# Sheet1.net
KiCad netlist of a schematic drawn in Altium Designer
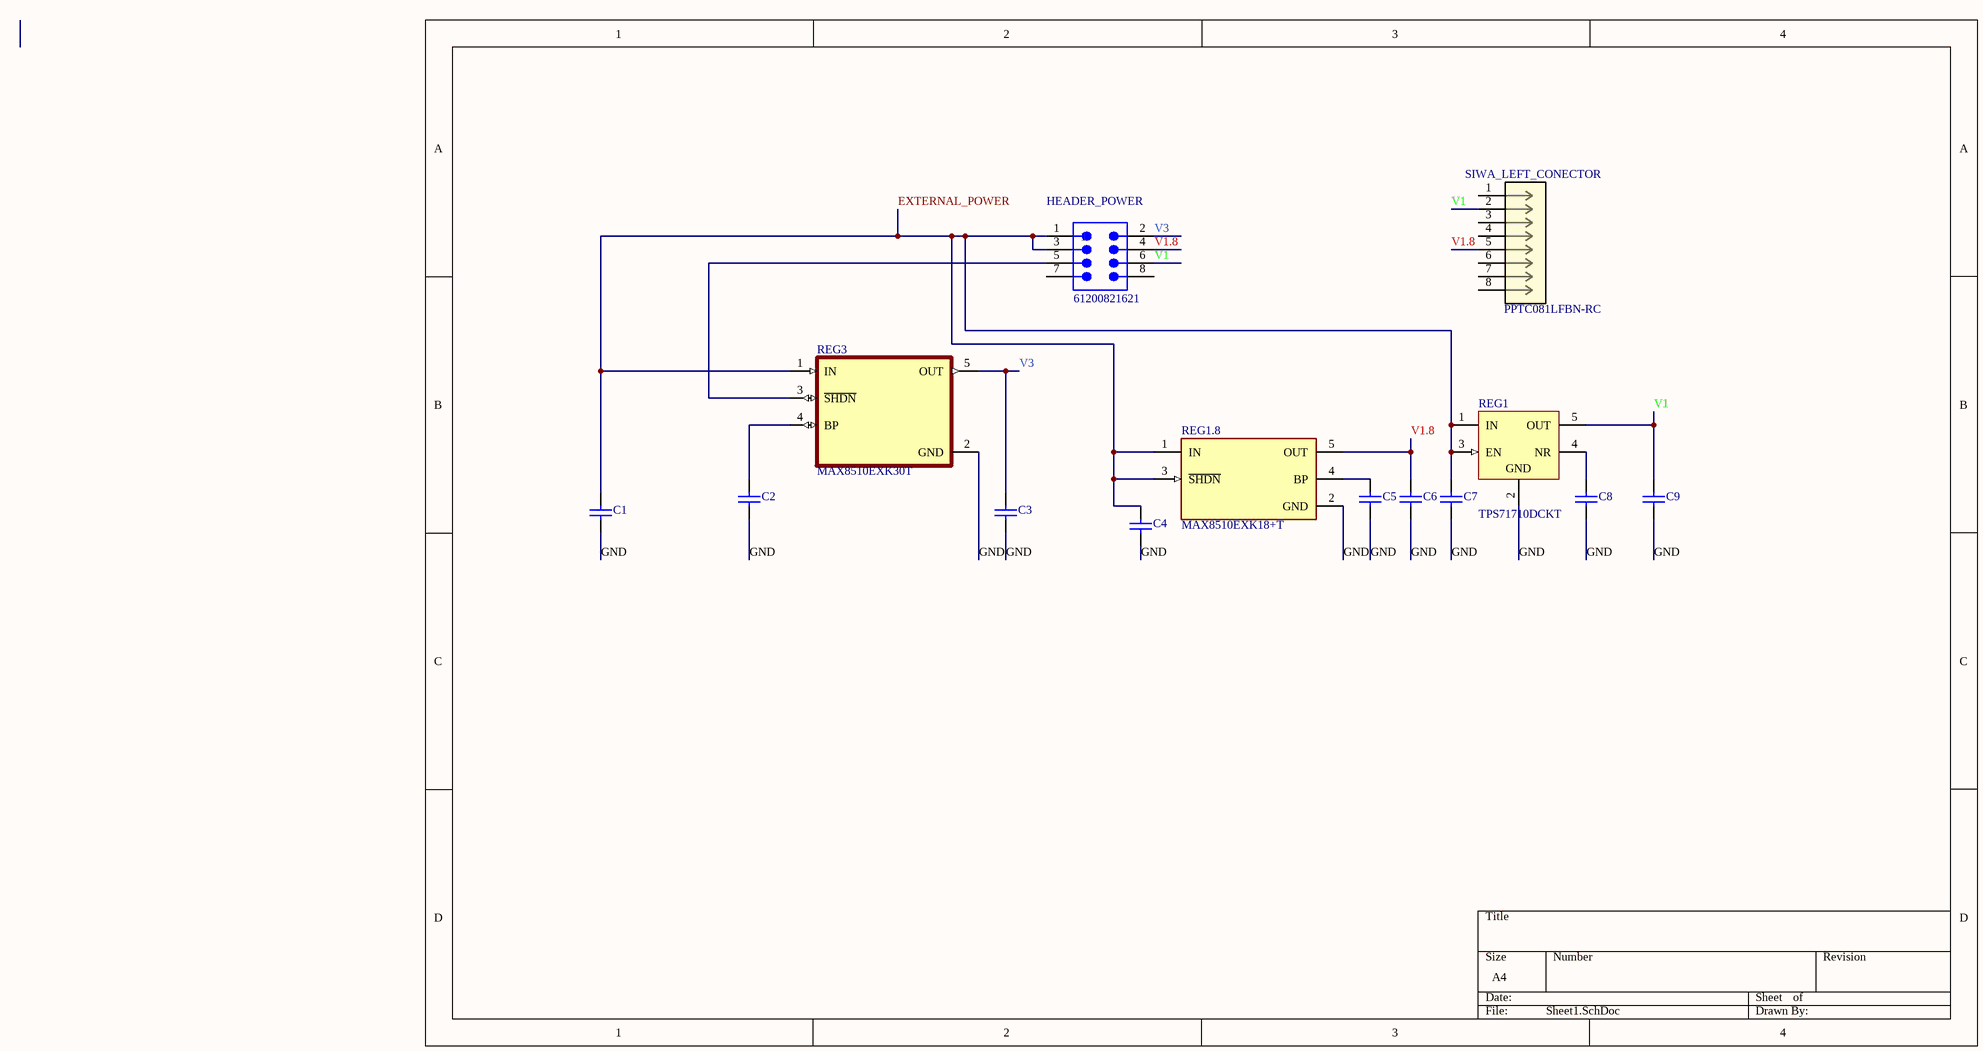
[diagram p0: Sheet1.SchDoc]

(export (version "E")
  (design (tool "Eeschema 10.0.6"))
  (components
    (comp (ref "C1")
      (value "VJ0603Y102KXJAC")
      (footprint "CAPC1608X92X38ML15T08")
      (fields (field (name "MANUFACTURER") "Vitramon"))
      (libsource (lib "Altium Content Vault") (part "CAP"))
    )
    (comp (ref "C2")
      (value "VJ0603Y102KXJAC")
      (footprint "CAPC1608X92X38ML15T08")
      (fields (field (name "MANUFACTURER") "Vitramon"))
      (libsource (lib "Altium Content Vault") (part "CAP"))
    )
    (comp (ref "C3")
      (value "VJ0603Y102KXJAC")
      (footprint "CAPC1608X92X38ML15T08")
      (fields (field (name "MANUFACTURER") "Vitramon"))
      (libsource (lib "Altium Content Vault") (part "CAP"))
    )
    (comp (ref "C4")
      (value "VJ0603Y102KXJAC")
      (footprint "CAPC1608X92X38ML15T08")
      (fields (field (name "MANUFACTURER") "Vitramon"))
      (libsource (lib "Altium Content Vault") (part "CAP"))
    )
    (comp (ref "C5")
      (value "VJ0603Y102KXJAC")
      (footprint "CAPC1608X92X38ML15T08")
      (fields (field (name "MANUFACTURER") "Vitramon"))
      (libsource (lib "Altium Content Vault") (part "CAP"))
    )
    (comp (ref "C6")
      (value "VJ0603Y102KXJAC")
      (footprint "CAPC1608X92X38ML15T08")
      (fields (field (name "MANUFACTURER") "Vitramon"))
      (libsource (lib "Altium Content Vault") (part "CAP"))
    )
    (comp (ref "C7")
      (value "VJ0603Y102KXJAC")
      (footprint "CAPC1608X92X38ML15T08")
      (fields (field (name "MANUFACTURER") "Vitramon"))
      (libsource (lib "Altium Content Vault") (part "CAP"))
    )
    (comp (ref "C8")
      (value "VJ0603Y102KXJAC")
      (footprint "CAPC1608X92X38ML15T08")
      (fields (field (name "MANUFACTURER") "Vitramon"))
      (libsource (lib "Altium Content Vault") (part "CAP"))
    )
    (comp (ref "C9")
      (value "VJ0603Y102KXJAC")
      (footprint "CAPC1608X92X38ML15T08")
      (fields (field (name "MANUFACTURER") "Vitramon"))
      (libsource (lib "Altium Content Vault") (part "CAP"))
    )
    (comp (ref "HEADER_POWER")
      (value "61200821621")
      (footprint "61200821621")
      (description "Wr-bhd; 2.54MM Pitch 8 Way 2 Row Shrouded Straight Pcb Header, Surface Mount")
      (libsource (lib "Altium Content Vault") (part "Header_Male_2R_08P"))
    )
    (comp (ref "REG1")
      (value "TPS71710DCKT")
      (footprint "DCK0005A_M")
      (fields (field (name "MANUFACTURER") "Texas Instruments"))
      (libsource (lib "Altium Content Vault") (part "TI-TPS79NXX-YYSOT5"))
    )
    (comp (ref "REG1.8")
      (value "MAX8510EXK18+T")
      (footprint "FP-X5-1-MFG")
      (description "IC REG LINEAR 1.8V 120MA SC70-5")
      (libsource (lib "Altium Content Vault") (part "355d6218c957986cfc1b3588039a240"))
    )
    (comp (ref "REG3")
      (value "MAX8510EXK30T")
      (footprint "SOT65P210X110-5N")
      (description "DoÄŸrusal Voltaj RegÃ¼latÃ¶rÃ¼ IC Pozitif Sabit 1 Ã‡Ä±kÄ±ÅŸ 120mA SC-70-5")
      (fields (field (name "MF") "Maxim Integrated Products") (field (name "MP") "MAX8510EXK30+T"))
      (libsource (lib "MAX8510EXK30T") (part "MAX8510EXK30T"))
    )
    (comp (ref "SIWA_LEFT_CONECTOR")
      (value "PPTC081LFBN-RC")
      (footprint "CONN_PPTC081LFBN-RC_SUL")
      (description "Description")
      (fields (field (name "COPYRIGHT") "Copyright (C) 2026 Ultra Librarian. All rights reserved."))
      (libsource (lib "PPTC081LFBN-RC") (part "PPTC081LFBN-RC"))
    )
  )
  (nets
    (net (code "1") (name "/EXTERNAL_POWER") (class "Default")
      (node (ref "C1") (pin "2") (pinfunction "2_2") (pintype "passive"))
      (node (ref "C4") (pin "2") (pinfunction "2_2") (pintype "passive"))
      (node (ref "C7") (pin "2") (pinfunction "2_2") (pintype "passive"))
      (node (ref "HEADER_POWER") (pin "1") (pinfunction "1_1") (pintype "passive"))
      (node (ref "HEADER_POWER") (pin "3") (pinfunction "3_3") (pintype "passive"))
      (node (ref "REG1") (pin "1") (pinfunction "IN_1") (pintype "power_in"))
      (node (ref "REG1") (pin "3") (pinfunction "EN_3") (pintype "input"))
      (node (ref "REG1.8") (pin "1") (pinfunction "IN_1") (pintype "power_in"))
      (node (ref "REG1.8") (pin "3") (pinfunction "~{SHDN}_3") (pintype "input"))
      (node (ref "REG3") (pin "1") (pinfunction "IN_1") (pintype "input"))
    )
    (net (code "2") (name "/GND") (class "Default")
      (node (ref "C1") (pin "1") (pinfunction "1_1") (pintype "passive"))
      (node (ref "C2") (pin "1") (pinfunction "1_1") (pintype "passive"))
      (node (ref "C3") (pin "1") (pinfunction "1_1") (pintype "passive"))
      (node (ref "C4") (pin "1") (pinfunction "1_1") (pintype "passive"))
      (node (ref "C5") (pin "1") (pinfunction "1_1") (pintype "passive"))
      (node (ref "C6") (pin "1") (pinfunction "1_1") (pintype "passive"))
      (node (ref "C7") (pin "1") (pinfunction "1_1") (pintype "passive"))
      (node (ref "C8") (pin "1") (pinfunction "1_1") (pintype "passive"))
      (node (ref "C9") (pin "1") (pinfunction "1_1") (pintype "passive"))
      (node (ref "REG1") (pin "2") (pinfunction "GND_2") (pintype "power_in"))
      (node (ref "REG1.8") (pin "2") (pinfunction "GND_2") (pintype "power_in"))
      (node (ref "REG3") (pin "2") (pinfunction "GND_2") (pintype "power_in"))
    )
    (net (code "3") (name "/V1") (class "Default")
      (node (ref "C9") (pin "2") (pinfunction "2_2") (pintype "passive"))
      (node (ref "HEADER_POWER") (pin "6") (pinfunction "6_6") (pintype "passive"))
      (node (ref "REG1") (pin "5") (pinfunction "OUT_5") (pintype "power_in"))
      (node (ref "SIWA_LEFT_CONECTOR") (pin "2") (pinfunction "2_2") (pintype "passive"))
    )
    (net (code "4") (name "/V1.8") (class "Default")
      (node (ref "C6") (pin "2") (pinfunction "2_2") (pintype "passive"))
      (node (ref "HEADER_POWER") (pin "4") (pinfunction "4_4") (pintype "passive"))
      (node (ref "REG1.8") (pin "5") (pinfunction "OUT_5") (pintype "power_in"))
      (node (ref "SIWA_LEFT_CONECTOR") (pin "5") (pinfunction "5_5") (pintype "passive"))
    )
    (net (code "5") (name "/V3") (class "Default")
      (node (ref "C3") (pin "2") (pinfunction "2_2") (pintype "passive"))
      (node (ref "HEADER_POWER") (pin "2") (pinfunction "2_2") (pintype "passive"))
      (node (ref "REG3") (pin "5") (pinfunction "OUT_5") (pintype "output"))
    )
    (net (code "6") (name "Net-(REG1-NR)") (class "Default")
      (node (ref "C8") (pin "2") (pinfunction "2_2") (pintype "passive"))
      (node (ref "REG1") (pin "4") (pinfunction "NR_4") (pintype "passive"))
    )
    (net (code "7") (name "Net-(REG1.8-BP)") (class "Default")
      (node (ref "C5") (pin "2") (pinfunction "2_2") (pintype "passive"))
      (node (ref "REG1.8") (pin "4") (pinfunction "BP_4") (pintype "passive"))
    )
    (net (code "8") (name "Net-(REG3-BP)") (class "Default")
      (node (ref "C2") (pin "2") (pinfunction "2_2") (pintype "passive"))
      (node (ref "REG3") (pin "4") (pinfunction "BP_4") (pintype "bidirectional"))
    )
    (net (code "9") (name "Net-(REG3-~{SHDN})") (class "Default")
      (node (ref "HEADER_POWER") (pin "5") (pinfunction "5_5") (pintype "passive"))
      (node (ref "REG3") (pin "3") (pinfunction "~{SHDN}_3") (pintype "bidirectional"))
    )
    (net (code "10") (name "unconnected-(HEADER_POWER-Pad7)") (class "Default")
      (node (ref "HEADER_POWER") (pin "7") (pinfunction "7_7") (pintype "passive"))
    )
    (net (code "11") (name "unconnected-(HEADER_POWER-Pad8)") (class "Default")
      (node (ref "HEADER_POWER") (pin "8") (pinfunction "8_8") (pintype "passive"))
    )
    (net (code "12") (name "unconnected-(SIWA_LEFT_CONECTOR-Pad1)") (class "Default")
      (node (ref "SIWA_LEFT_CONECTOR") (pin "1") (pinfunction "1_1") (pintype "passive"))
    )
    (net (code "13") (name "unconnected-(SIWA_LEFT_CONECTOR-Pad3)") (class "Default")
      (node (ref "SIWA_LEFT_CONECTOR") (pin "3") (pinfunction "3_3") (pintype "passive"))
    )
    (net (code "14") (name "unconnected-(SIWA_LEFT_CONECTOR-Pad4)") (class "Default")
      (node (ref "SIWA_LEFT_CONECTOR") (pin "4") (pinfunction "4_4") (pintype "passive"))
    )
    (net (code "15") (name "unconnected-(SIWA_LEFT_CONECTOR-Pad6)") (class "Default")
      (node (ref "SIWA_LEFT_CONECTOR") (pin "6") (pinfunction "6_6") (pintype "passive"))
    )
    (net (code "16") (name "unconnected-(SIWA_LEFT_CONECTOR-Pad7)") (class "Default")
      (node (ref "SIWA_LEFT_CONECTOR") (pin "7") (pinfunction "7_7") (pintype "passive"))
    )
    (net (code "17") (name "unconnected-(SIWA_LEFT_CONECTOR-Pad8)") (class "Default")
      (node (ref "SIWA_LEFT_CONECTOR") (pin "8") (pinfunction "8_8") (pintype "passive"))
    )
  )
)
